# untitled.net
KiCad netlist of a schematic drawn in EAGLE
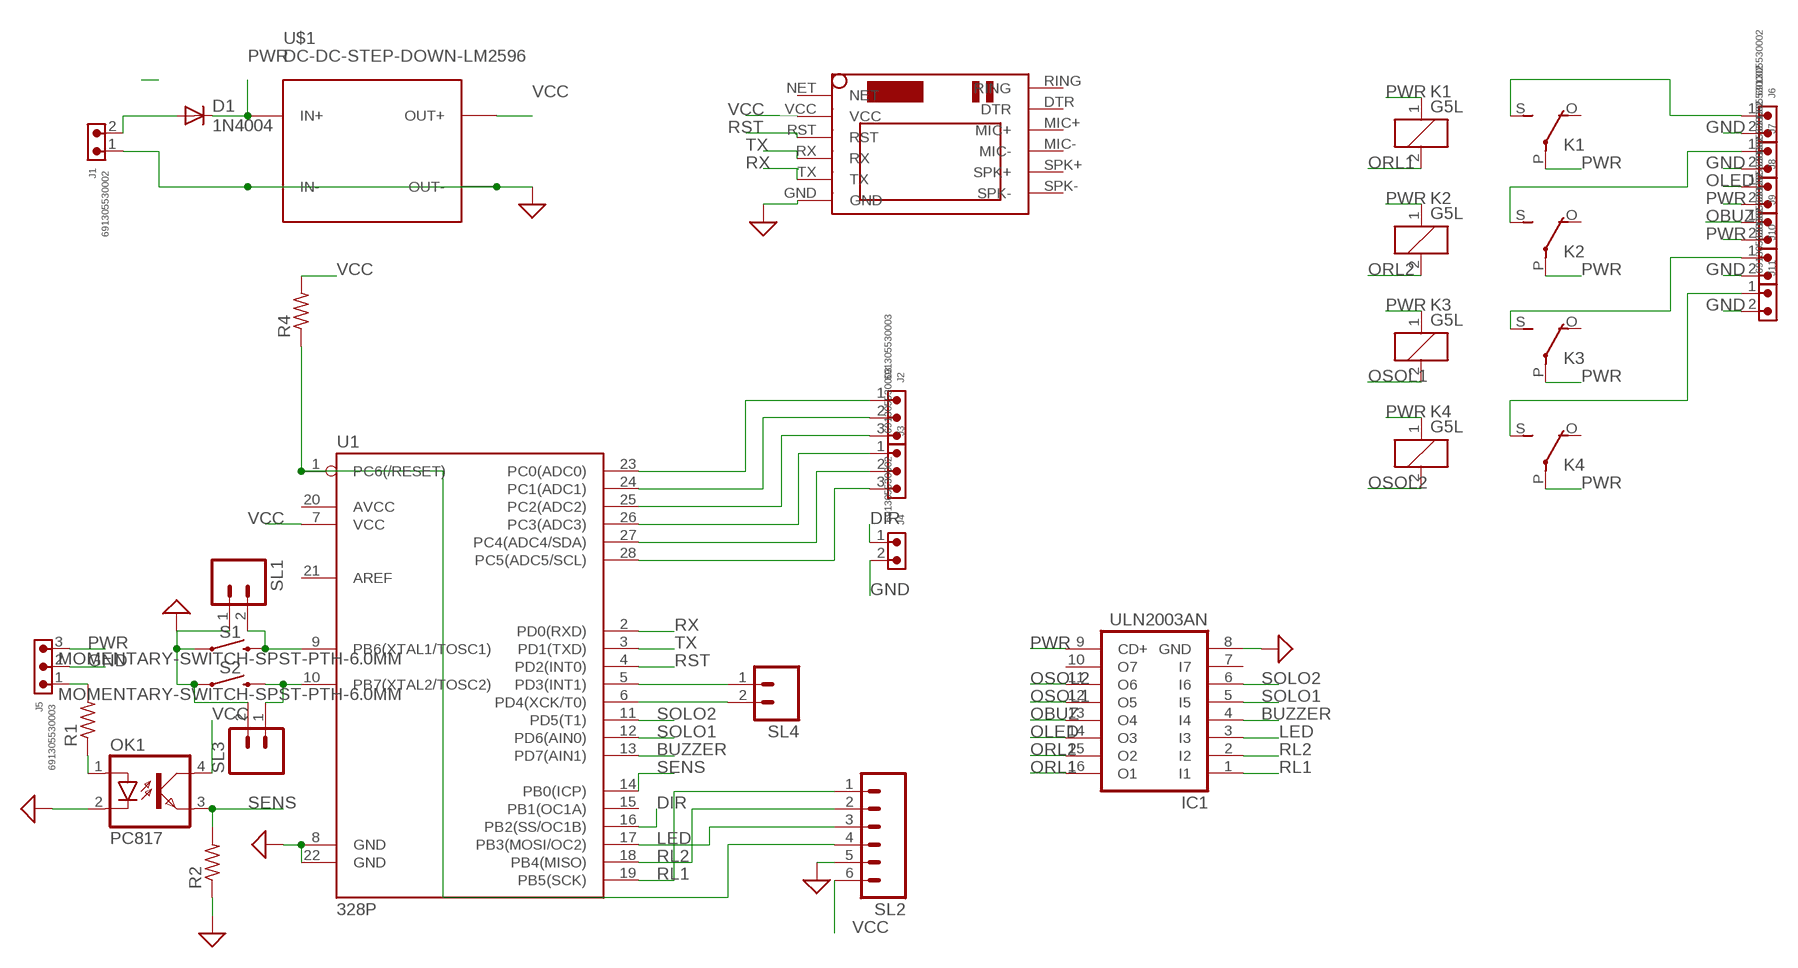
[diagram p0: schematic, sheet 1]

(export (version "E")
  (design (tool "Eeschema 10.0.6"))
  (components
    (comp (ref "D1")
      (value "1N4004")
      (footprint "eagle-import:DO41-10")
      (libsource (lib "eagle-import") (part "1N4004"))
    )
    (comp (ref "IC1")
      (value "ULN2003AN")
      (footprint "eagle-import:DIL16")
      (libsource (lib "eagle-import") (part "ULN2003AN"))
    )
    (comp (ref "J1")
      (value "691305530002")
      (footprint "eagle-import:691305530002")
      (libsource (lib "eagle-import") (part "691305530002"))
    )
    (comp (ref "J2")
      (value "691305530003")
      (footprint "eagle-import:691305530003")
      (libsource (lib "eagle-import") (part "691305530003"))
    )
    (comp (ref "J3")
      (value "691305530003")
      (footprint "eagle-import:691305530003")
      (libsource (lib "eagle-import") (part "691305530003"))
    )
    (comp (ref "J4")
      (value "691305530002")
      (footprint "eagle-import:691305530002")
      (libsource (lib "eagle-import") (part "691305530002"))
    )
    (comp (ref "J5")
      (value "691305530003")
      (footprint "eagle-import:691305530003")
      (libsource (lib "eagle-import") (part "691305530003"))
    )
    (comp (ref "J6")
      (value "691305530002")
      (footprint "eagle-import:691305530002")
      (libsource (lib "eagle-import") (part "691305530002"))
    )
    (comp (ref "J7")
      (value "691305530002")
      (footprint "eagle-import:691305530002")
      (libsource (lib "eagle-import") (part "691305530002"))
    )
    (comp (ref "J8")
      (value "691305530002")
      (footprint "eagle-import:691305530002")
      (libsource (lib "eagle-import") (part "691305530002"))
    )
    (comp (ref "J9")
      (value "691305530002")
      (footprint "eagle-import:691305530002")
      (libsource (lib "eagle-import") (part "691305530002"))
    )
    (comp (ref "J10")
      (value "691305530002")
      (footprint "eagle-import:691305530002")
      (libsource (lib "eagle-import") (part "691305530002"))
    )
    (comp (ref "J11")
      (value "691305530002")
      (footprint "eagle-import:691305530002")
      (libsource (lib "eagle-import") (part "691305530002"))
    )
    (comp (ref "K1")
      (value "G5L")
      (footprint "eagle-import:G5LE")
      (libsource (lib "eagle-import") (part "G5L"))
    )
    (comp (ref "K2")
      (value "G5L")
      (footprint "eagle-import:G5LE")
      (libsource (lib "eagle-import") (part "G5L"))
    )
    (comp (ref "K3")
      (value "G5L")
      (footprint "eagle-import:G5LE")
      (libsource (lib "eagle-import") (part "G5L"))
    )
    (comp (ref "K4")
      (value "G5L")
      (footprint "eagle-import:G5LE")
      (libsource (lib "eagle-import") (part "G5L"))
    )
    (comp (ref "OK1")
      (value "PC817")
      (footprint "eagle-import:DIL04")
      (fields (field (name "MPN") "PC817X4J000F"))
      (libsource (lib "eagle-import") (part "PC817"))
    )
    (comp (ref "R1")
      (value "R-US_0207/10")
      (footprint "eagle-import:0207_10")
      (libsource (lib "eagle-import") (part "adafruit_R-US_0207/10"))
    )
    (comp (ref "R2")
      (value "R-US_0207/10")
      (footprint "eagle-import:0207_10")
      (libsource (lib "eagle-import") (part "R-US_0207/10"))
    )
    (comp (ref "R4")
      (value "R-US_0207/10")
      (footprint "eagle-import:0207_10")
      (libsource (lib "eagle-import") (part "R-US_0207/10"))
    )
    (comp (ref "S1")
      (value "MOMENTARY-SWITCH-SPST-PTH-6.0MM")
      (footprint "eagle-import:TACTILE_SWITCH_PTH_6.0MM")
      (libsource (lib "eagle-import") (part "MOMENTARY-SWITCH-SPST-PTH-6.0MM"))
    )
    (comp (ref "S2")
      (value "MOMENTARY-SWITCH-SPST-PTH-6.0MM")
      (footprint "eagle-import:TACTILE_SWITCH_PTH_6.0MM")
      (libsource (lib "eagle-import") (part "MOMENTARY-SWITCH-SPST-PTH-6.0MM"))
    )
    (comp (ref "SL1")
      (value "M02")
      (footprint "eagle-import:02P")
      (libsource (lib "eagle-import") (part "M02"))
    )
    (comp (ref "SL2")
      (value "M06")
      (footprint "eagle-import:06P")
      (libsource (lib "eagle-import") (part "M06"))
    )
    (comp (ref "SL3")
      (value "M02")
      (footprint "eagle-import:02P")
      (libsource (lib "eagle-import") (part "M02"))
    )
    (comp (ref "SL4")
      (value "M02")
      (footprint "eagle-import:02P")
      (libsource (lib "eagle-import") (part "M02"))
    )
    (comp (ref "U$1")
      (value "DC-DC-STEP-DOWN-LM2596")
      (footprint "eagle-import:DC-DC-STEP-DOWN-LM2596")
      (libsource (lib "eagle-import") (part "DC-DC-STEP-DOWN-LM2596"))
    )
    (comp (ref "U$2")
      (value "SIM800LMODULE")
      (footprint "eagle-import:SIM800LMODULE")
      (libsource (lib "eagle-import") (part "SIM800LMODULE"))
    )
    (comp (ref "U1")
      (value "328P")
      (footprint "eagle-import:DIP28")
      (libsource (lib "eagle-import") (part "ATMEGA328P_PDIP"))
    )
  )
  (nets
    (net (code "1") (name "/BUZZER") (class "Default")
      (node (ref "IC1") (pin "4") (pinfunction "I4_4") (pintype "input"))
      (node (ref "U1") (pin "13") (pinfunction "PD7(AIN1)_13") (pintype "bidirectional"))
    )
    (net (code "2") (name "/DIR") (class "Default")
      (node (ref "J4") (pin "1") (pinfunction "1_1") (pintype "passive"))
      (node (ref "U1") (pin "16") (pinfunction "PB2(SS/OC1B)_16") (pintype "bidirectional"))
    )
    (net (code "3") (name "/LED") (class "Default")
      (node (ref "IC1") (pin "3") (pinfunction "I3_3") (pintype "input"))
      (node (ref "SL2") (pin "3") (pinfunction "3_3") (pintype "passive"))
      (node (ref "U1") (pin "17") (pinfunction "PB3(MOSI/OC2)_17") (pintype "bidirectional"))
    )
    (net (code "4") (name "/OBUZ") (class "Default")
      (node (ref "IC1") (pin "13") (pinfunction "O4_13") (pintype "open_collector"))
      (node (ref "J9") (pin "1") (pinfunction "1_1") (pintype "passive"))
    )
    (net (code "5") (name "/OLED") (class "Default")
      (node (ref "IC1") (pin "14") (pinfunction "O3_14") (pintype "open_collector"))
      (node (ref "J8") (pin "1") (pinfunction "1_1") (pintype "passive"))
    )
    (net (code "6") (name "/ORL1") (class "Default")
      (node (ref "IC1") (pin "16") (pinfunction "O1_16") (pintype "open_collector"))
      (node (ref "K1") (pin "2") (pinfunction "2_2") (pintype "passive"))
    )
    (net (code "7") (name "/ORL2") (class "Default")
      (node (ref "IC1") (pin "15") (pinfunction "O2_15") (pintype "open_collector"))
      (node (ref "K2") (pin "2") (pinfunction "2_2") (pintype "passive"))
    )
    (net (code "8") (name "/OSOL1") (class "Default")
      (node (ref "IC1") (pin "12") (pinfunction "O5_12") (pintype "open_collector"))
      (node (ref "K3") (pin "2") (pinfunction "2_2") (pintype "passive"))
    )
    (net (code "9") (name "/OSOL2") (class "Default")
      (node (ref "IC1") (pin "11") (pinfunction "O6_11") (pintype "open_collector"))
      (node (ref "K4") (pin "2") (pinfunction "2_2") (pintype "passive"))
    )
    (net (code "10") (name "/PWR") (class "Default")
      (node (ref "D1") (pin "C") (pinfunction "C_C") (pintype "passive"))
      (node (ref "IC1") (pin "9") (pinfunction "CD+_9") (pintype "passive"))
      (node (ref "J5") (pin "3") (pinfunction "3_3") (pintype "passive"))
      (node (ref "J8") (pin "2") (pinfunction "2_2") (pintype "passive"))
      (node (ref "J9") (pin "2") (pinfunction "2_2") (pintype "passive"))
      (node (ref "K1") (pin "1") (pinfunction "1_1") (pintype "passive"))
      (node (ref "K1") (pin "P") (pinfunction "P_P") (pintype "passive"))
      (node (ref "K2") (pin "1") (pinfunction "1_1") (pintype "passive"))
      (node (ref "K2") (pin "P") (pinfunction "P_P") (pintype "passive"))
      (node (ref "K3") (pin "1") (pinfunction "1_1") (pintype "passive"))
      (node (ref "K3") (pin "P") (pinfunction "P_P") (pintype "passive"))
      (node (ref "K4") (pin "1") (pinfunction "1_1") (pintype "passive"))
      (node (ref "K4") (pin "P") (pinfunction "P_P") (pintype "passive"))
      (node (ref "U$1") (pin "IN+") (pinfunction "IN+_IN+") (pintype "bidirectional"))
    )
    (net (code "11") (name "/RL1") (class "Default")
      (node (ref "IC1") (pin "1") (pinfunction "I1_1") (pintype "input"))
      (node (ref "SL2") (pin "1") (pinfunction "1_1") (pintype "passive"))
      (node (ref "U1") (pin "19") (pinfunction "PB5(SCK)_19") (pintype "bidirectional"))
    )
    (net (code "12") (name "/RL2") (class "Default")
      (node (ref "IC1") (pin "2") (pinfunction "I2_2") (pintype "input"))
      (node (ref "SL2") (pin "2") (pinfunction "2_2") (pintype "passive"))
      (node (ref "U1") (pin "18") (pinfunction "PB4(MISO)_18") (pintype "bidirectional"))
    )
    (net (code "13") (name "/RST") (class "Default")
      (node (ref "U$2") (pin "RST") (pinfunction "RST_RST") (pintype "bidirectional"))
      (node (ref "U1") (pin "4") (pinfunction "PD2(INT0)_4") (pintype "bidirectional"))
    )
    (net (code "14") (name "/RX") (class "Default")
      (node (ref "U$2") (pin "TX") (pinfunction "TX_TX") (pintype "bidirectional"))
      (node (ref "U1") (pin "2") (pinfunction "PD0(RXD)_2") (pintype "bidirectional"))
    )
    (net (code "15") (name "/SENS") (class "Default")
      (node (ref "OK1") (pin "3") (pinfunction "EMIT_3") (pintype "passive"))
      (node (ref "R2") (pin "2") (pinfunction "2_2") (pintype "passive"))
      (node (ref "U1") (pin "14") (pinfunction "PB0(ICP)_14") (pintype "bidirectional"))
    )
    (net (code "16") (name "/SOLO1") (class "Default")
      (node (ref "IC1") (pin "5") (pinfunction "I5_5") (pintype "input"))
      (node (ref "U1") (pin "12") (pinfunction "PD6(AIN0)_12") (pintype "bidirectional"))
    )
    (net (code "17") (name "/SOLO2") (class "Default")
      (node (ref "IC1") (pin "6") (pinfunction "I6_6") (pintype "input"))
      (node (ref "U1") (pin "11") (pinfunction "PD5(T1)_11") (pintype "bidirectional"))
    )
    (net (code "18") (name "/TX") (class "Default")
      (node (ref "U$2") (pin "RX") (pinfunction "RX_RX") (pintype "bidirectional"))
      (node (ref "U1") (pin "3") (pinfunction "PD1(TXD)_3") (pintype "bidirectional"))
    )
    (net (code "19") (name "/VCC") (class "Default")
      (node (ref "OK1") (pin "4") (pinfunction "COL_4") (pintype "passive"))
      (node (ref "R4") (pin "2") (pinfunction "2_2") (pintype "passive"))
      (node (ref "SL2") (pin "6") (pinfunction "6_6") (pintype "passive"))
      (node (ref "U$1") (pin "OUT+") (pinfunction "OUT+_OUT+") (pintype "bidirectional"))
      (node (ref "U$2") (pin "VCC") (pinfunction "VCC_VCC") (pintype "bidirectional"))
      (node (ref "U1") (pin "7") (pinfunction "VCC_7") (pintype "bidirectional"))
    )
    (net (code "20") (name "Net-(D1-PadA)") (class "Default")
      (node (ref "D1") (pin "A") (pinfunction "A_A") (pintype "passive"))
      (node (ref "J1") (pin "2") (pinfunction "2_2") (pintype "passive"))
    )
    (net (code "21") (name "Net-(J5-Pad1)") (class "Default")
      (node (ref "J5") (pin "1") (pinfunction "1_1") (pintype "passive"))
      (node (ref "R1") (pin "2") (pinfunction "2_2") (pintype "passive"))
    )
    (net (code "22") (name "Net-(J6-Pad1)") (class "Default")
      (node (ref "J6") (pin "1") (pinfunction "1_1") (pintype "passive"))
      (node (ref "K1") (pin "S") (pinfunction "S_S") (pintype "passive"))
    )
    (net (code "23") (name "Net-(J7-Pad1)") (class "Default")
      (node (ref "J7") (pin "1") (pinfunction "1_1") (pintype "passive"))
      (node (ref "K2") (pin "S") (pinfunction "S_S") (pintype "passive"))
    )
    (net (code "24") (name "Net-(J10-Pad1)") (class "Default")
      (node (ref "J10") (pin "1") (pinfunction "1_1") (pintype "passive"))
      (node (ref "K3") (pin "S") (pinfunction "S_S") (pintype "passive"))
    )
    (net (code "25") (name "Net-(J11-Pad1)") (class "Default")
      (node (ref "J11") (pin "1") (pinfunction "1_1") (pintype "passive"))
      (node (ref "K4") (pin "S") (pinfunction "S_S") (pintype "passive"))
    )
    (net (code "26") (name "Net-(OK1-A)") (class "Default")
      (node (ref "OK1") (pin "1") (pinfunction "A_1") (pintype "passive"))
      (node (ref "R1") (pin "1") (pinfunction "1_1") (pintype "passive"))
    )
    (net (code "27") (name "Net-(S1-2)") (class "Default")
      (node (ref "S1") (pin "3") (pinfunction "2_3") (pintype "passive"))
      (node (ref "SL1") (pin "2") (pinfunction "2_2") (pintype "passive"))
      (node (ref "U1") (pin "9") (pinfunction "PB6(XTAL1/TOSC1)_9") (pintype "bidirectional"))
    )
    (net (code "28") (name "Net-(S2-2)") (class "Default")
      (node (ref "S2") (pin "3") (pinfunction "2_3") (pintype "passive"))
      (node (ref "SL3") (pin "1") (pinfunction "1_1") (pintype "passive"))
      (node (ref "U1") (pin "10") (pinfunction "PB7(XTAL2/TOSC2)_10") (pintype "bidirectional"))
    )
    (net (code "29") (name "Net-(U1-PC0(ADC0))") (class "Default")
      (node (ref "J2") (pin "1") (pinfunction "1_1") (pintype "passive"))
      (node (ref "U1") (pin "23") (pinfunction "PC0(ADC0)_23") (pintype "bidirectional"))
    )
    (net (code "30") (name "Net-(U1-PC1(ADC1))") (class "Default")
      (node (ref "J2") (pin "2") (pinfunction "2_2") (pintype "passive"))
      (node (ref "U1") (pin "24") (pinfunction "PC1(ADC1)_24") (pintype "bidirectional"))
    )
    (net (code "31") (name "Net-(U1-PC2(ADC2))") (class "Default")
      (node (ref "J2") (pin "3") (pinfunction "3_3") (pintype "passive"))
      (node (ref "U1") (pin "25") (pinfunction "PC2(ADC2)_25") (pintype "bidirectional"))
    )
    (net (code "32") (name "Net-(U1-PC3(ADC3))") (class "Default")
      (node (ref "J3") (pin "1") (pinfunction "1_1") (pintype "passive"))
      (node (ref "U1") (pin "26") (pinfunction "PC3(ADC3)_26") (pintype "bidirectional"))
    )
    (net (code "33") (name "Net-(U1-PC4(ADC4{slash}SDA))") (class "Default")
      (node (ref "J3") (pin "2") (pinfunction "2_2") (pintype "passive"))
      (node (ref "U1") (pin "27") (pinfunction "PC4(ADC4/SDA)_27") (pintype "bidirectional"))
    )
    (net (code "34") (name "Net-(U1-PC5(ADC5{slash}SCL))") (class "Default")
      (node (ref "J3") (pin "3") (pinfunction "3_3") (pintype "passive"))
      (node (ref "U1") (pin "28") (pinfunction "PC5(ADC5/SCL)_28") (pintype "bidirectional"))
    )
    (net (code "35") (name "Net-(U1-PC6({slash}RESET))") (class "Default")
      (node (ref "R4") (pin "1") (pinfunction "1_1") (pintype "passive"))
      (node (ref "SL2") (pin "4") (pinfunction "4_4") (pintype "passive"))
      (node (ref "U1") (pin "1") (pinfunction "PC6(/RESET)_1") (pintype "bidirectional"))
    )
    (net (code "36") (name "Net-(U1-PD3(INT1))") (class "Default")
      (node (ref "SL4") (pin "1") (pinfunction "1_1") (pintype "passive"))
      (node (ref "U1") (pin "5") (pinfunction "PD3(INT1)_5") (pintype "bidirectional"))
    )
    (net (code "37") (name "Net-(U1-PD4(XCK{slash}T0))") (class "Default")
      (node (ref "SL4") (pin "2") (pinfunction "2_2") (pintype "passive"))
      (node (ref "U1") (pin "6") (pinfunction "PD4(XCK/T0)_6") (pintype "bidirectional"))
    )
    (net (code "38") (name "SUP") (class "Default")
      (node (ref "IC1") (pin "8") (pinfunction "GND_8") (pintype "power_in"))
      (node (ref "J1") (pin "1") (pinfunction "1_1") (pintype "passive"))
      (node (ref "J10") (pin "2") (pinfunction "2_2") (pintype "passive"))
      (node (ref "J11") (pin "2") (pinfunction "2_2") (pintype "passive"))
      (node (ref "J4") (pin "2") (pinfunction "2_2") (pintype "passive"))
      (node (ref "J5") (pin "2") (pinfunction "2_2") (pintype "passive"))
      (node (ref "J6") (pin "2") (pinfunction "2_2") (pintype "passive"))
      (node (ref "J7") (pin "2") (pinfunction "2_2") (pintype "passive"))
      (node (ref "OK1") (pin "2") (pinfunction "C_2") (pintype "passive"))
      (node (ref "R2") (pin "1") (pinfunction "1_1") (pintype "passive"))
      (node (ref "S1") (pin "1") (pinfunction "1_1") (pintype "passive"))
      (node (ref "S2") (pin "1") (pinfunction "1_1") (pintype "passive"))
      (node (ref "SL1") (pin "1") (pinfunction "1_1") (pintype "passive"))
      (node (ref "SL2") (pin "5") (pinfunction "5_5") (pintype "passive"))
      (node (ref "SL3") (pin "2") (pinfunction "2_2") (pintype "passive"))
      (node (ref "U$1") (pin "IN-") (pinfunction "IN-_IN-") (pintype "bidirectional"))
      (node (ref "U$1") (pin "OUT-") (pinfunction "OUT-_OUT-") (pintype "bidirectional"))
      (node (ref "U$2") (pin "GND") (pinfunction "GND_GND") (pintype "bidirectional"))
      (node (ref "U1") (pin "22") (pinfunction "GND_22") (pintype "bidirectional"))
      (node (ref "U1") (pin "8") (pinfunction "GND_8") (pintype "bidirectional"))
    )
    (net (code "39") (name "unconnected-(IC1-I7-Pad7)") (class "Default")
      (node (ref "IC1") (pin "7") (pinfunction "I7_7") (pintype "input"))
    )
    (net (code "40") (name "unconnected-(IC1-O7-Pad10)") (class "Default")
      (node (ref "IC1") (pin "10") (pinfunction "O7_10") (pintype "open_collector"))
    )
    (net (code "41") (name "unconnected-(K1-PadO)") (class "Default")
      (node (ref "K1") (pin "O") (pinfunction "O_O") (pintype "passive"))
    )
    (net (code "42") (name "unconnected-(K2-PadO)") (class "Default")
      (node (ref "K2") (pin "O") (pinfunction "O_O") (pintype "passive"))
    )
    (net (code "43") (name "unconnected-(K3-PadO)") (class "Default")
      (node (ref "K3") (pin "O") (pinfunction "O_O") (pintype "passive"))
    )
    (net (code "44") (name "unconnected-(K4-PadO)") (class "Default")
      (node (ref "K4") (pin "O") (pinfunction "O_O") (pintype "passive"))
    )
    (net (code "45") (name "unconnected-(U$2-PadDTR)") (class "Default")
      (node (ref "U$2") (pin "DTR") (pinfunction "DTR_DTR") (pintype "bidirectional"))
    )
    (net (code "46") (name "unconnected-(U$2-PadMIC+)") (class "Default")
      (node (ref "U$2") (pin "MIC+") (pinfunction "MIC+_MIC+") (pintype "bidirectional"))
    )
    (net (code "47") (name "unconnected-(U$2-PadMIC-)") (class "Default")
      (node (ref "U$2") (pin "MIC-") (pinfunction "MIC-_MIC-") (pintype "bidirectional"))
    )
    (net (code "48") (name "unconnected-(U$2-PadNET)") (class "Default")
      (node (ref "U$2") (pin "NET") (pinfunction "NET_NET") (pintype "bidirectional"))
    )
    (net (code "49") (name "unconnected-(U$2-PadRING)") (class "Default")
      (node (ref "U$2") (pin "RING") (pinfunction "RING_RING") (pintype "bidirectional"))
    )
    (net (code "50") (name "unconnected-(U$2-PadSPK+)") (class "Default")
      (node (ref "U$2") (pin "SPK+") (pinfunction "SPK+_SPK+") (pintype "bidirectional"))
    )
    (net (code "51") (name "unconnected-(U$2-PadSPK-)") (class "Default")
      (node (ref "U$2") (pin "SPK-") (pinfunction "SPK-_SPK-") (pintype "bidirectional"))
    )
    (net (code "52") (name "unconnected-(U1-AREF-Pad21)") (class "Default")
      (node (ref "U1") (pin "21") (pinfunction "AREF_21") (pintype "bidirectional"))
    )
    (net (code "53") (name "unconnected-(U1-AVCC-Pad20)") (class "Default")
      (node (ref "U1") (pin "20") (pinfunction "AVCC_20") (pintype "bidirectional"))
    )
    (net (code "54") (name "unconnected-(U1-PB1(OC1A)-Pad15)") (class "Default")
      (node (ref "U1") (pin "15") (pinfunction "PB1(OC1A)_15") (pintype "bidirectional"))
    )
  )
)
